# sparkfun_esp32_environment_sensor_shield.net
KiCad netlist of a schematic drawn in EAGLE
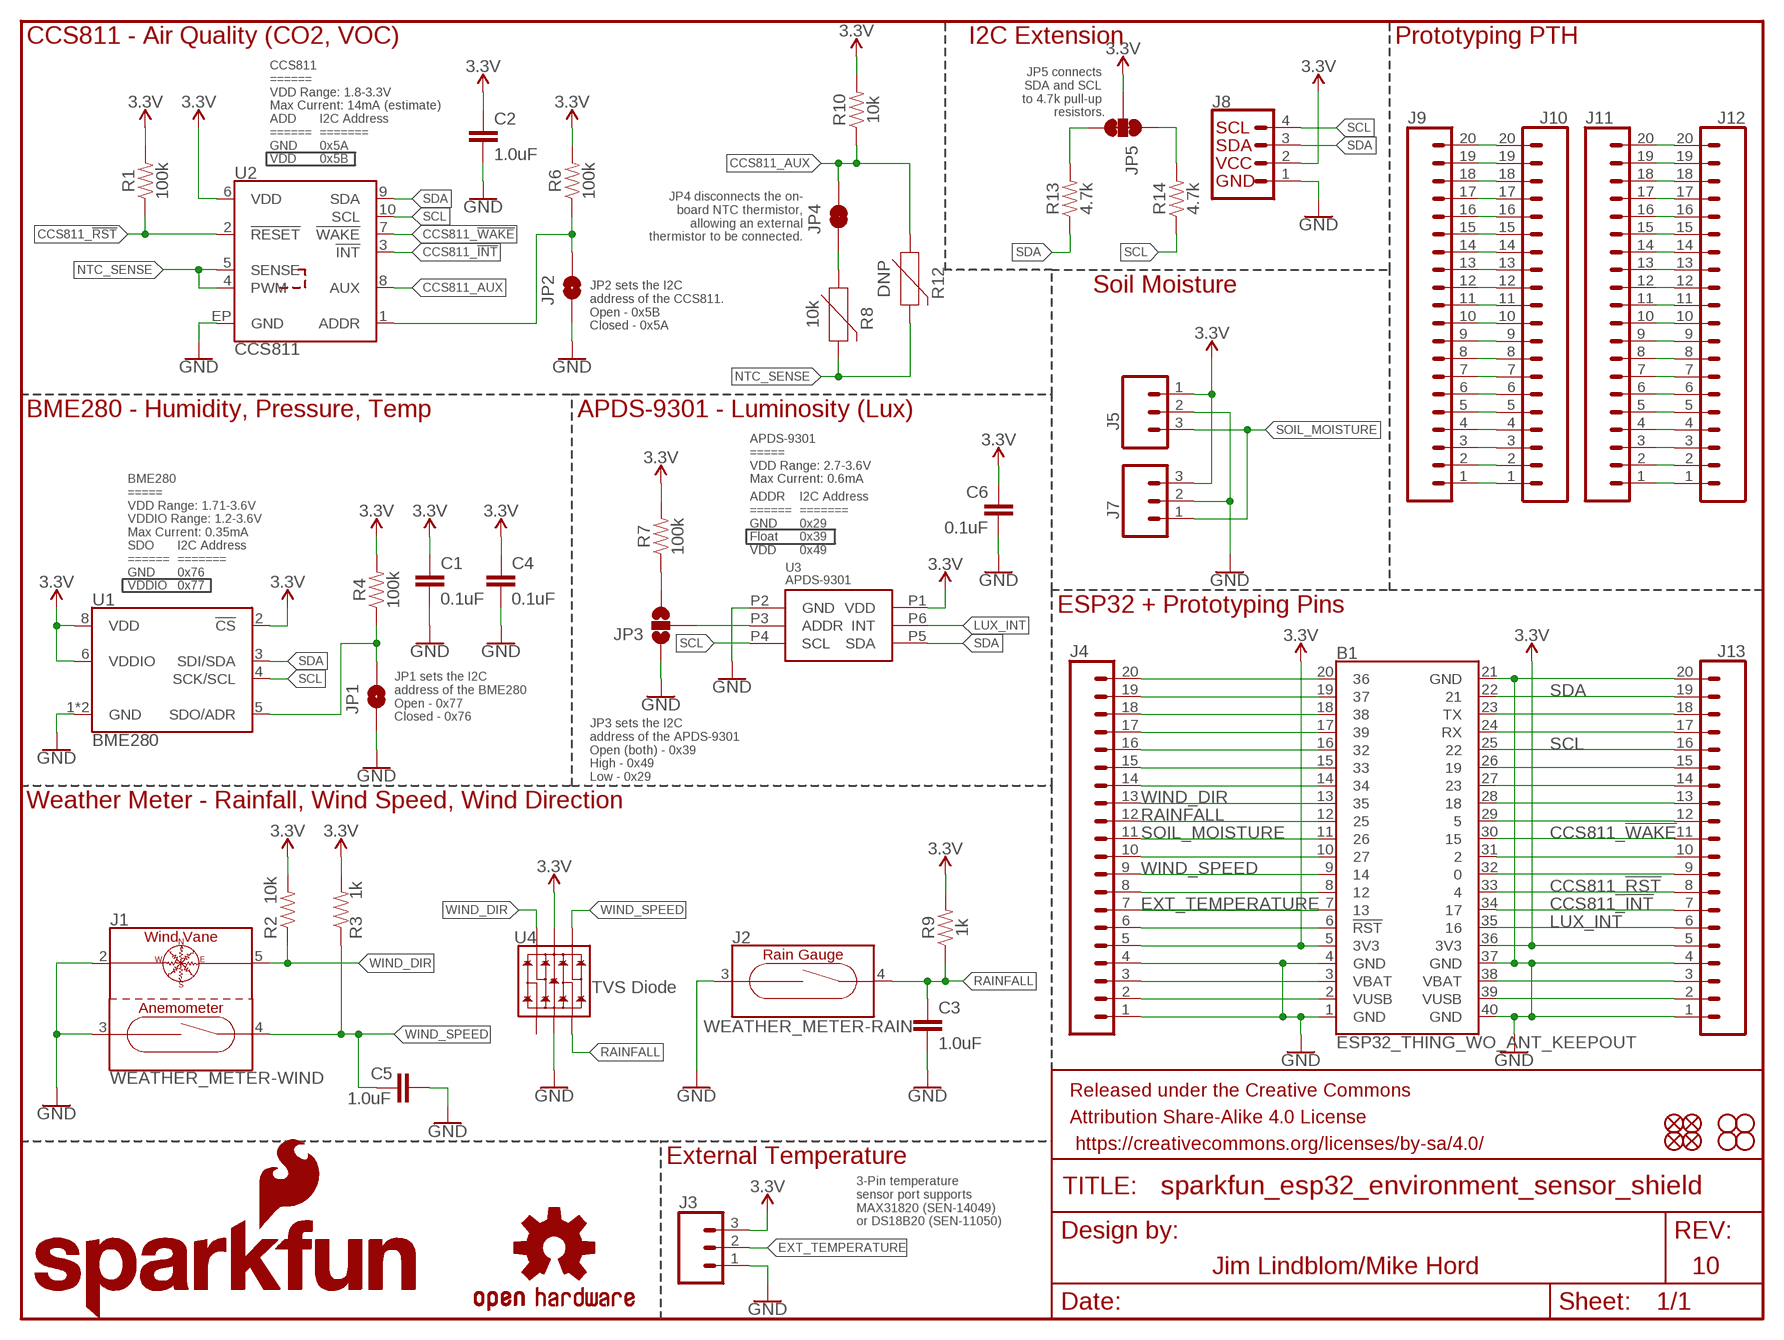
[diagram p0: schematic, sheet 1]

(export (version "E")
  (design (tool "Eeschema 10.0.6"))
  (components
    (comp (ref "B1")
      (value "ESP32_THING_WO_ANT_KEEPOUT")
      (footprint "eagle-import:ESP32_THING_NO_ANT")
      (libsource (lib "eagle-import") (part "ESP32_THING_WO_ANT_KEEPOUT"))
    )
    (comp (ref "C1")
      (value "0.1uF")
      (footprint "eagle-import:0603")
      (libsource (lib "eagle-import") (part "0.1UF-0603-25V-(+80/-20%)"))
    )
    (comp (ref "C2")
      (value "1.0uF")
      (footprint "eagle-import:0603")
      (libsource (lib "eagle-import") (part "1.0UF-0603-16V-10%"))
    )
    (comp (ref "C3")
      (value "1.0uF")
      (footprint "eagle-import:0603")
      (libsource (lib "eagle-import") (part "1.0UF-0603-16V-10%"))
    )
    (comp (ref "C4")
      (value "0.1uF")
      (footprint "eagle-import:0603")
      (libsource (lib "eagle-import") (part "0.1UF-0603-25V-(+80/-20%)"))
    )
    (comp (ref "C5")
      (value "1.0uF")
      (footprint "eagle-import:0603")
      (libsource (lib "eagle-import") (part "1.0UF-0603-16V-10%"))
    )
    (comp (ref "C6")
      (value "0.1uF")
      (footprint "eagle-import:0603")
      (libsource (lib "eagle-import") (part "0.1UF-0603-25V-(+80/-20%)"))
    )
    (comp (ref "FD1")
      (value "FIDUCIAL1X2")
      (footprint "eagle-import:FIDUCIAL-1X2")
      (libsource (lib "eagle-import") (part "FIDUCIAL1X2"))
    )
    (comp (ref "FD2")
      (value "FIDUCIAL1X2")
      (footprint "eagle-import:FIDUCIAL-1X2")
      (libsource (lib "eagle-import") (part "FIDUCIAL1X2"))
    )
    (comp (ref "FD3")
      (value "FIDUCIAL1X2")
      (footprint "eagle-import:FIDUCIAL-1X2")
      (libsource (lib "eagle-import") (part "FIDUCIAL1X2"))
    )
    (comp (ref "FD4")
      (value "FIDUCIAL1X2")
      (footprint "eagle-import:FIDUCIAL-1X2")
      (libsource (lib "eagle-import") (part "FIDUCIAL1X2"))
    )
    (comp (ref "FRAME1")
      (value "FRAME-LETTER")
      (footprint "eagle-import:CREATIVE_COMMONS")
      (libsource (lib "eagle-import") (part "FRAME-LETTER"))
    )
    (comp (ref "H1")
      (value "STAND-OFF")
      (footprint "eagle-import:STAND-OFF")
      (libsource (lib "eagle-import") (part "STAND-OFF"))
    )
    (comp (ref "H2")
      (value "STAND-OFF")
      (footprint "eagle-import:STAND-OFF")
      (libsource (lib "eagle-import") (part "STAND-OFF"))
    )
    (comp (ref "H3")
      (value "STAND-OFF")
      (footprint "eagle-import:STAND-OFF")
      (libsource (lib "eagle-import") (part "STAND-OFF"))
    )
    (comp (ref "H4")
      (value "STAND-OFF")
      (footprint "eagle-import:STAND-OFF")
      (libsource (lib "eagle-import") (part "STAND-OFF"))
    )
    (comp (ref "J1")
      (value "WEATHER_METER-WIND")
      (footprint "eagle-import:RJ11-6")
      (libsource (lib "eagle-import") (part "WEATHER_METER-WIND"))
    )
    (comp (ref "J2")
      (value "WEATHER_METER-RAIN")
      (footprint "eagle-import:RJ11-6")
      (libsource (lib "eagle-import") (part "WEATHER_METER-RAIN"))
    )
    (comp (ref "J3")
      (value "CONN_03")
      (footprint "eagle-import:1X03")
      (libsource (lib "eagle-import") (part "CONN_03"))
    )
    (comp (ref "J4")
      (value "CONN_20NOSILK")
      (footprint "eagle-import:1X20_NOSILK")
      (libsource (lib "eagle-import") (part "CONN_20NOSILK"))
    )
    (comp (ref "J5")
      (value "CONN_03")
      (footprint "eagle-import:1X03")
      (libsource (lib "eagle-import") (part "CONN_03"))
    )
    (comp (ref "J7")
      (value "CONN_03SCREW-NS")
      (footprint "eagle-import:SCREWTERMINAL-3.5MM-3-NS")
      (libsource (lib "eagle-import") (part "CONN_03SCREW-NS"))
    )
    (comp (ref "J8")
      (value "I2C_STANDARD")
      (footprint "eagle-import:1X04")
      (libsource (lib "eagle-import") (part "I2C_STANDARD"))
    )
    (comp (ref "J9")
      (value "CONN_20NOSILK")
      (footprint "eagle-import:1X20_NOSILK")
      (libsource (lib "eagle-import") (part "CONN_20NOSILK"))
    )
    (comp (ref "J10")
      (value "CONN_20NOSILK")
      (footprint "eagle-import:1X20_NOSILK")
      (libsource (lib "eagle-import") (part "CONN_20NOSILK"))
    )
    (comp (ref "J11")
      (value "CONN_20NOSILK")
      (footprint "eagle-import:1X20_NOSILK")
      (libsource (lib "eagle-import") (part "CONN_20NOSILK"))
    )
    (comp (ref "J12")
      (value "CONN_20NOSILK")
      (footprint "eagle-import:1X20_NOSILK")
      (libsource (lib "eagle-import") (part "CONN_20NOSILK"))
    )
    (comp (ref "J13")
      (value "CONN_20NOSILK")
      (footprint "eagle-import:1X20_NOSILK")
      (libsource (lib "eagle-import") (part "CONN_20NOSILK"))
    )
    (comp (ref "JP1")
      (value "JUMPER-SMT_2_NO_SILK")
      (footprint "eagle-import:SMT-JUMPER_2_NO_SILK")
      (libsource (lib "eagle-import") (part "JUMPER-SMT_2_NO_SILK"))
    )
    (comp (ref "JP2")
      (value "JUMPER-SMT_2_NO_SILK")
      (footprint "eagle-import:SMT-JUMPER_2_NO_SILK")
      (libsource (lib "eagle-import") (part "JUMPER-SMT_2_NO_SILK"))
    )
    (comp (ref "JP3")
      (value "JUMPER-SMT_3_NO_SILK")
      (footprint "eagle-import:SMT-JUMPER_3_NO_SILK")
      (libsource (lib "eagle-import") (part "JUMPER-SMT_3_NO_SILK"))
    )
    (comp (ref "JP4")
      (value "JUMPER-SMT_2_NC_TRACE_SILK")
      (footprint "eagle-import:SMT-JUMPER_2_NC_TRACE_SILK")
      (libsource (lib "eagle-import") (part "JUMPER-SMT_2_NC_TRACE_SILK"))
    )
    (comp (ref "JP5")
      (value "JUMPER-SMT_3_2-NC_TRACE_SILK")
      (footprint "eagle-import:SMT-JUMPER_3_2-NC_TRACE_SILK")
      (libsource (lib "eagle-import") (part "JUMPER-SMT_3_2-NC_TRACE_SILK"))
    )
    (comp (ref "LOGO1")
      (value "SFE_LOGO_NAME.1_INCH")
      (footprint "eagle-import:SFE_LOGO_NAME_.1")
      (libsource (lib "eagle-import") (part "SFE_LOGO_NAME.1_INCH"))
    )
    (comp (ref "LOGO2")
      (value "SFE_LOGO_NAME_FLAME.1_INCH")
      (footprint "eagle-import:SFE_LOGO_NAME_FLAME_.1")
      (libsource (lib "eagle-import") (part "SFE_LOGO_NAME_FLAME.1_INCH"))
    )
    (comp (ref "LOGO3")
      (value "SFE_LOGO_FLAME.1_INCH")
      (footprint "eagle-import:SFE_LOGO_FLAME_.1")
      (libsource (lib "eagle-import") (part "SFE_LOGO_FLAME.1_INCH"))
    )
    (comp (ref "LOGO4")
      (value "OSHW-LOGOS")
      (footprint "eagle-import:OSHW-LOGO-S")
      (libsource (lib "eagle-import") (part "OSHW-LOGOS"))
    )
    (comp (ref "R1")
      (value "100k")
      (footprint "eagle-import:0603")
      (libsource (lib "eagle-import") (part "100KOHM-0603-1/10W-1%"))
    )
    (comp (ref "R2")
      (value "10k")
      (footprint "eagle-import:0603")
      (libsource (lib "eagle-import") (part "10KOHM-0603-1/10W-1%"))
    )
    (comp (ref "R3")
      (value "1k")
      (footprint "eagle-import:0603")
      (libsource (lib "eagle-import") (part "1KOHM-0603-1/10W-1%"))
    )
    (comp (ref "R4")
      (value "100k")
      (footprint "eagle-import:0603")
      (libsource (lib "eagle-import") (part "100KOHM-0603-1/10W-1%"))
    )
    (comp (ref "R6")
      (value "100k")
      (footprint "eagle-import:0603")
      (libsource (lib "eagle-import") (part "100KOHM-0603-1/10W-1%"))
    )
    (comp (ref "R7")
      (value "100k")
      (footprint "eagle-import:0603")
      (libsource (lib "eagle-import") (part "100KOHM-0603-1/10W-1%"))
    )
    (comp (ref "R8")
      (value "10k")
      (footprint "eagle-import:0603")
      (libsource (lib "eagle-import") (part "NTC-THERMISTOR-0603"))
    )
    (comp (ref "R9")
      (value "1k")
      (footprint "eagle-import:0603")
      (libsource (lib "eagle-import") (part "1KOHM-0603-1/10W-1%"))
    )
    (comp (ref "R10")
      (value "10k")
      (footprint "eagle-import:0603")
      (libsource (lib "eagle-import") (part "10KOHM-0603-1/10W-1%"))
    )
    (comp (ref "R12")
      (value "DNP")
      (footprint "eagle-import:AXIAL-0.1")
      (libsource (lib "eagle-import") (part "NTC-THERMISTOR-AXIAL-0.1"))
    )
    (comp (ref "R13")
      (value "4.7k")
      (footprint "eagle-import:0603")
      (libsource (lib "eagle-import") (part "4.7KOHM-0603-1/10W-1%"))
    )
    (comp (ref "R14")
      (value "4.7k")
      (footprint "eagle-import:0603")
      (libsource (lib "eagle-import") (part "4.7KOHM-0603-1/10W-1%"))
    )
    (comp (ref "U1")
      (value "BME280")
      (footprint "eagle-import:LGA-8-2.5X2.5")
      (libsource (lib "eagle-import") (part "BME280"))
    )
    (comp (ref "U2")
      (value "CCS811")
      (footprint "eagle-import:LGA10-2.7X4.0MM")
      (libsource (lib "eagle-import") (part "CCS811"))
    )
    (comp (ref "U3")
      (value "APDS-9301")
      (footprint "eagle-import:CHIPLED-6")
      (libsource (lib "eagle-import") (part "APDS-9301"))
    )
    (comp (ref "U4")
      (value "TVS Diode")
      (footprint "eagle-import:SOT-23-6")
      (libsource (lib "eagle-import") (part "TVS_DIODE_ARRAYSMD"))
    )
  )
  (nets
    (net (code "1") (name "/CCS811_~{INT}") (class "Default")
      (node (ref "B1") (pin "34") (pinfunction "17_34") (pintype "bidirectional"))
      (node (ref "J13") (pin "7") (pinfunction "7_7") (pintype "passive"))
      (node (ref "U2") (pin "3") (pinfunction "~{INT}_3") (pintype "bidirectional"))
    )
    (net (code "2") (name "/CCS811_~{RST}") (class "Default")
      (node (ref "B1") (pin "33") (pinfunction "4_33") (pintype "bidirectional"))
      (node (ref "J13") (pin "8") (pinfunction "8_8") (pintype "passive"))
      (node (ref "R1") (pin "1") (pinfunction "1_1") (pintype "passive"))
      (node (ref "U2") (pin "2") (pinfunction "~{RESET}_2") (pintype "bidirectional"))
    )
    (net (code "3") (name "/CCS811_~{WAKE}") (class "Default")
      (node (ref "B1") (pin "30") (pinfunction "15_30") (pintype "bidirectional"))
      (node (ref "J13") (pin "11") (pinfunction "11_11") (pintype "passive"))
      (node (ref "U2") (pin "7") (pinfunction "~{WAKE}_7") (pintype "bidirectional"))
    )
    (net (code "4") (name "3.3V") (class "Default")
      (node (ref "B1") (pin "36") (pinfunction "3V3_36") (pintype "bidirectional"))
      (node (ref "B1") (pin "5") (pinfunction "3V3_5") (pintype "bidirectional"))
      (node (ref "C1") (pin "1") (pinfunction "1_1") (pintype "passive"))
      (node (ref "C2") (pin "1") (pinfunction "1_1") (pintype "passive"))
      (node (ref "C4") (pin "1") (pinfunction "1_1") (pintype "passive"))
      (node (ref "C6") (pin "1") (pinfunction "1_1") (pintype "passive"))
      (node (ref "J13") (pin "5") (pinfunction "5_5") (pintype "passive"))
      (node (ref "J3") (pin "3") (pinfunction "3_3") (pintype "passive"))
      (node (ref "J4") (pin "5") (pinfunction "5_5") (pintype "passive"))
      (node (ref "J5") (pin "1") (pinfunction "1_1") (pintype "passive"))
      (node (ref "J7") (pin "3") (pinfunction "3_3") (pintype "passive"))
      (node (ref "J8") (pin "2") (pinfunction "2_2") (pintype "power_in"))
      (node (ref "JP5") (pin "2") (pinfunction "2_2") (pintype "passive"))
      (node (ref "R1") (pin "2") (pinfunction "2_2") (pintype "passive"))
      (node (ref "R10") (pin "2") (pinfunction "2_2") (pintype "passive"))
      (node (ref "R2") (pin "2") (pinfunction "2_2") (pintype "passive"))
      (node (ref "R3") (pin "2") (pinfunction "2_2") (pintype "passive"))
      (node (ref "R4") (pin "2") (pinfunction "2_2") (pintype "passive"))
      (node (ref "R6") (pin "2") (pinfunction "2_2") (pintype "passive"))
      (node (ref "R7") (pin "2") (pinfunction "2_2") (pintype "passive"))
      (node (ref "R9") (pin "2") (pinfunction "2_2") (pintype "passive"))
      (node (ref "U1") (pin "2") (pinfunction "~{CS}_2") (pintype "bidirectional"))
      (node (ref "U1") (pin "6") (pinfunction "VDDIO_6") (pintype "bidirectional"))
      (node (ref "U1") (pin "8") (pinfunction "VDD_8") (pintype "bidirectional"))
      (node (ref "U2") (pin "6") (pinfunction "VDD_6") (pintype "bidirectional"))
      (node (ref "U3") (pin "P1") (pinfunction "VDD_P1") (pintype "bidirectional"))
      (node (ref "U4") (pin "5") (pinfunction "VCC_5") (pintype "bidirectional"))
    )
    (net (code "5") (name "CCS811_AUX") (class "Default")
      (node (ref "JP4") (pin "2") (pinfunction "2_2") (pintype "passive"))
      (node (ref "R10") (pin "1") (pinfunction "1_1") (pintype "passive"))
      (node (ref "R12") (pin "P$1") (pinfunction "1_P$1") (pintype "bidirectional"))
      (node (ref "U2") (pin "8") (pinfunction "AUX_8") (pintype "bidirectional"))
    )
    (net (code "6") (name "EXT_TEMPERATURE") (class "Default")
      (node (ref "B1") (pin "7") (pinfunction "13_7") (pintype "bidirectional"))
      (node (ref "J3") (pin "2") (pinfunction "2_2") (pintype "passive"))
      (node (ref "J4") (pin "7") (pinfunction "7_7") (pintype "passive"))
    )
    (net (code "7") (name "GND") (class "Default")
      (node (ref "B1") (pin "1") (pinfunction "GND_1") (pintype "bidirectional"))
      (node (ref "B1") (pin "21") (pinfunction "GND_21") (pintype "bidirectional"))
      (node (ref "B1") (pin "37") (pinfunction "GND_37") (pintype "bidirectional"))
      (node (ref "B1") (pin "4") (pinfunction "GND_4") (pintype "bidirectional"))
      (node (ref "B1") (pin "40") (pinfunction "GND_40") (pintype "bidirectional"))
      (node (ref "C1") (pin "2") (pinfunction "2_2") (pintype "passive"))
      (node (ref "C2") (pin "2") (pinfunction "2_2") (pintype "passive"))
      (node (ref "C3") (pin "2") (pinfunction "2_2") (pintype "passive"))
      (node (ref "C4") (pin "2") (pinfunction "2_2") (pintype "passive"))
      (node (ref "C5") (pin "2") (pinfunction "2_2") (pintype "passive"))
      (node (ref "C6") (pin "2") (pinfunction "2_2") (pintype "passive"))
      (node (ref "J1") (pin "2") (pinfunction "DIR-1_2") (pintype "bidirectional"))
      (node (ref "J1") (pin "3") (pinfunction "ANN-1_3") (pintype "bidirectional"))
      (node (ref "J13") (pin "1") (pinfunction "1_1") (pintype "passive"))
      (node (ref "J13") (pin "20") (pinfunction "20_20") (pintype "passive"))
      (node (ref "J13") (pin "4") (pinfunction "4_4") (pintype "passive"))
      (node (ref "J2") (pin "3") (pinfunction "1_3") (pintype "passive"))
      (node (ref "J3") (pin "1") (pinfunction "1_1") (pintype "passive"))
      (node (ref "J4") (pin "1") (pinfunction "1_1") (pintype "passive"))
      (node (ref "J4") (pin "4") (pinfunction "4_4") (pintype "passive"))
      (node (ref "J5") (pin "2") (pinfunction "2_2") (pintype "passive"))
      (node (ref "J7") (pin "2") (pinfunction "2_2") (pintype "passive"))
      (node (ref "J8") (pin "1") (pinfunction "1_1") (pintype "power_in"))
      (node (ref "JP1") (pin "1") (pinfunction "1_1") (pintype "passive"))
      (node (ref "JP2") (pin "1") (pinfunction "1_1") (pintype "passive"))
      (node (ref "JP3") (pin "1") (pinfunction "1_1") (pintype "passive"))
      (node (ref "U1") (pin "1") (pinfunction "GND_1") (pintype "bidirectional"))
      (node (ref "U1") (pin "7") (pinfunction "GND_7") (pintype "bidirectional"))
      (node (ref "U2") (pin "EP") (pinfunction "GND_EP") (pintype "bidirectional"))
      (node (ref "U3") (pin "P2") (pinfunction "GND_P2") (pintype "bidirectional"))
      (node (ref "U4") (pin "2") (pinfunction "VSS_2") (pintype "bidirectional"))
    )
    (net (code "8") (name "LUX_INT") (class "Default")
      (node (ref "B1") (pin "35") (pinfunction "16_35") (pintype "bidirectional"))
      (node (ref "J13") (pin "6") (pinfunction "6_6") (pintype "passive"))
      (node (ref "U3") (pin "P6") (pinfunction "INT_P6") (pintype "bidirectional"))
    )
    (net (code "9") (name "NTC_SENSE") (class "Default")
      (node (ref "R12") (pin "P$2") (pinfunction "2_P$2") (pintype "bidirectional"))
      (node (ref "R8") (pin "2") (pinfunction "2_2") (pintype "bidirectional"))
      (node (ref "U2") (pin "4") (pinfunction "PWM_4") (pintype "bidirectional"))
      (node (ref "U2") (pin "5") (pinfunction "SENSE_5") (pintype "bidirectional"))
    )
    (net (code "10") (name "Net-(B1-0)") (class "Default")
      (node (ref "B1") (pin "32") (pinfunction "0_32") (pintype "bidirectional"))
      (node (ref "J13") (pin "9") (pinfunction "9_9") (pintype "passive"))
    )
    (net (code "11") (name "Net-(B1-2)") (class "Default")
      (node (ref "B1") (pin "31") (pinfunction "2_31") (pintype "bidirectional"))
      (node (ref "J13") (pin "10") (pinfunction "10_10") (pintype "passive"))
    )
    (net (code "12") (name "Net-(B1-5)") (class "Default")
      (node (ref "B1") (pin "29") (pinfunction "5_29") (pintype "bidirectional"))
      (node (ref "J13") (pin "12") (pinfunction "12_12") (pintype "passive"))
    )
    (net (code "13") (name "Net-(B1-12)") (class "Default")
      (node (ref "B1") (pin "8") (pinfunction "12_8") (pintype "bidirectional"))
      (node (ref "J4") (pin "8") (pinfunction "8_8") (pintype "passive"))
    )
    (net (code "14") (name "Net-(B1-18)") (class "Default")
      (node (ref "B1") (pin "28") (pinfunction "18_28") (pintype "bidirectional"))
      (node (ref "J13") (pin "13") (pinfunction "13_13") (pintype "passive"))
    )
    (net (code "15") (name "Net-(B1-19)") (class "Default")
      (node (ref "B1") (pin "26") (pinfunction "19_26") (pintype "bidirectional"))
      (node (ref "J13") (pin "15") (pinfunction "15_15") (pintype "passive"))
    )
    (net (code "16") (name "Net-(B1-23)") (class "Default")
      (node (ref "B1") (pin "27") (pinfunction "23_27") (pintype "bidirectional"))
      (node (ref "J13") (pin "14") (pinfunction "14_14") (pintype "passive"))
    )
    (net (code "17") (name "Net-(B1-27)") (class "Default")
      (node (ref "B1") (pin "10") (pinfunction "27_10") (pintype "bidirectional"))
      (node (ref "J4") (pin "10") (pinfunction "10_10") (pintype "passive"))
    )
    (net (code "18") (name "Net-(B1-32)") (class "Default")
      (node (ref "B1") (pin "16") (pinfunction "32_16") (pintype "bidirectional"))
      (node (ref "J4") (pin "16") (pinfunction "16_16") (pintype "passive"))
    )
    (net (code "19") (name "Net-(B1-33)") (class "Default")
      (node (ref "B1") (pin "15") (pinfunction "33_15") (pintype "bidirectional"))
      (node (ref "J4") (pin "15") (pinfunction "15_15") (pintype "passive"))
    )
    (net (code "20") (name "Net-(B1-34)") (class "Default")
      (node (ref "B1") (pin "14") (pinfunction "34_14") (pintype "bidirectional"))
      (node (ref "J4") (pin "14") (pinfunction "14_14") (pintype "passive"))
    )
    (net (code "21") (name "Net-(B1-36)") (class "Default")
      (node (ref "B1") (pin "20") (pinfunction "36_20") (pintype "bidirectional"))
      (node (ref "J4") (pin "20") (pinfunction "20_20") (pintype "passive"))
    )
    (net (code "22") (name "Net-(B1-37)") (class "Default")
      (node (ref "B1") (pin "19") (pinfunction "37_19") (pintype "bidirectional"))
      (node (ref "J4") (pin "19") (pinfunction "19_19") (pintype "passive"))
    )
    (net (code "23") (name "Net-(B1-38)") (class "Default")
      (node (ref "B1") (pin "18") (pinfunction "38_18") (pintype "bidirectional"))
      (node (ref "J4") (pin "18") (pinfunction "18_18") (pintype "passive"))
    )
    (net (code "24") (name "Net-(B1-39)") (class "Default")
      (node (ref "B1") (pin "17") (pinfunction "39_17") (pintype "bidirectional"))
      (node (ref "J4") (pin "17") (pinfunction "17_17") (pintype "passive"))
    )
    (net (code "25") (name "Net-(B1-RX)") (class "Default")
      (node (ref "B1") (pin "24") (pinfunction "RX_24") (pintype "bidirectional"))
      (node (ref "J13") (pin "17") (pinfunction "17_17") (pintype "passive"))
    )
    (net (code "26") (name "Net-(B1-TX)") (class "Default")
      (node (ref "B1") (pin "23") (pinfunction "TX_23") (pintype "bidirectional"))
      (node (ref "J13") (pin "18") (pinfunction "18_18") (pintype "passive"))
    )
    (net (code "27") (name "Net-(B1-VBAT-Pad3)") (class "Default")
      (node (ref "B1") (pin "3") (pinfunction "VBAT_3") (pintype "bidirectional"))
      (node (ref "J4") (pin "3") (pinfunction "3_3") (pintype "passive"))
    )
    (net (code "28") (name "Net-(B1-VBAT-Pad38)") (class "Default")
      (node (ref "B1") (pin "38") (pinfunction "VBAT_38") (pintype "bidirectional"))
      (node (ref "J13") (pin "3") (pinfunction "3_3") (pintype "passive"))
    )
    (net (code "29") (name "Net-(B1-VUSB-Pad2)") (class "Default")
      (node (ref "B1") (pin "2") (pinfunction "VUSB_2") (pintype "bidirectional"))
      (node (ref "J4") (pin "2") (pinfunction "2_2") (pintype "passive"))
    )
    (net (code "30") (name "Net-(B1-VUSB-Pad39)") (class "Default")
      (node (ref "B1") (pin "39") (pinfunction "VUSB_39") (pintype "bidirectional"))
      (node (ref "J13") (pin "2") (pinfunction "2_2") (pintype "passive"))
    )
    (net (code "31") (name "Net-(B1-~{RST})") (class "Default")
      (node (ref "B1") (pin "6") (pinfunction "~{RST}_6") (pintype "bidirectional"))
      (node (ref "J4") (pin "6") (pinfunction "6_6") (pintype "passive"))
    )
    (net (code "32") (name "Net-(J10-Pad1)") (class "Default")
      (node (ref "J10") (pin "1") (pinfunction "1_1") (pintype "passive"))
      (node (ref "J9") (pin "1") (pinfunction "1_1") (pintype "passive"))
    )
    (net (code "33") (name "Net-(J10-Pad2)") (class "Default")
      (node (ref "J10") (pin "2") (pinfunction "2_2") (pintype "passive"))
      (node (ref "J9") (pin "2") (pinfunction "2_2") (pintype "passive"))
    )
    (net (code "34") (name "Net-(J10-Pad3)") (class "Default")
      (node (ref "J10") (pin "3") (pinfunction "3_3") (pintype "passive"))
      (node (ref "J9") (pin "3") (pinfunction "3_3") (pintype "passive"))
    )
    (net (code "35") (name "Net-(J10-Pad4)") (class "Default")
      (node (ref "J10") (pin "4") (pinfunction "4_4") (pintype "passive"))
      (node (ref "J9") (pin "4") (pinfunction "4_4") (pintype "passive"))
    )
    (net (code "36") (name "Net-(J10-Pad5)") (class "Default")
      (node (ref "J10") (pin "5") (pinfunction "5_5") (pintype "passive"))
      (node (ref "J9") (pin "5") (pinfunction "5_5") (pintype "passive"))
    )
    (net (code "37") (name "Net-(J10-Pad6)") (class "Default")
      (node (ref "J10") (pin "6") (pinfunction "6_6") (pintype "passive"))
      (node (ref "J9") (pin "6") (pinfunction "6_6") (pintype "passive"))
    )
    (net (code "38") (name "Net-(J10-Pad7)") (class "Default")
      (node (ref "J10") (pin "7") (pinfunction "7_7") (pintype "passive"))
      (node (ref "J9") (pin "7") (pinfunction "7_7") (pintype "passive"))
    )
    (net (code "39") (name "Net-(J10-Pad8)") (class "Default")
      (node (ref "J10") (pin "8") (pinfunction "8_8") (pintype "passive"))
      (node (ref "J9") (pin "8") (pinfunction "8_8") (pintype "passive"))
    )
    (net (code "40") (name "Net-(J10-Pad9)") (class "Default")
      (node (ref "J10") (pin "9") (pinfunction "9_9") (pintype "passive"))
      (node (ref "J9") (pin "9") (pinfunction "9_9") (pintype "passive"))
    )
    (net (code "41") (name "Net-(J10-Pad10)") (class "Default")
      (node (ref "J10") (pin "10") (pinfunction "10_10") (pintype "passive"))
      (node (ref "J9") (pin "10") (pinfunction "10_10") (pintype "passive"))
    )
    (net (code "42") (name "Net-(J10-Pad11)") (class "Default")
      (node (ref "J10") (pin "11") (pinfunction "11_11") (pintype "passive"))
      (node (ref "J9") (pin "11") (pinfunction "11_11") (pintype "passive"))
    )
    (net (code "43") (name "Net-(J10-Pad12)") (class "Default")
      (node (ref "J10") (pin "12") (pinfunction "12_12") (pintype "passive"))
      (node (ref "J9") (pin "12") (pinfunction "12_12") (pintype "passive"))
    )
    (net (code "44") (name "Net-(J10-Pad13)") (class "Default")
      (node (ref "J10") (pin "13") (pinfunction "13_13") (pintype "passive"))
      (node (ref "J9") (pin "13") (pinfunction "13_13") (pintype "passive"))
    )
    (net (code "45") (name "Net-(J10-Pad14)") (class "Default")
      (node (ref "J10") (pin "14") (pinfunction "14_14") (pintype "passive"))
      (node (ref "J9") (pin "14") (pinfunction "14_14") (pintype "passive"))
    )
    (net (code "46") (name "Net-(J10-Pad15)") (class "Default")
      (node (ref "J10") (pin "15") (pinfunction "15_15") (pintype "passive"))
      (node (ref "J9") (pin "15") (pinfunction "15_15") (pintype "passive"))
    )
    (net (code "47") (name "Net-(J10-Pad16)") (class "Default")
      (node (ref "J10") (pin "16") (pinfunction "16_16") (pintype "passive"))
      (node (ref "J9") (pin "16") (pinfunction "16_16") (pintype "passive"))
    )
    (net (code "48") (name "Net-(J10-Pad17)") (class "Default")
      (node (ref "J10") (pin "17") (pinfunction "17_17") (pintype "passive"))
      (node (ref "J9") (pin "17") (pinfunction "17_17") (pintype "passive"))
    )
    (net (code "49") (name "Net-(J10-Pad18)") (class "Default")
      (node (ref "J10") (pin "18") (pinfunction "18_18") (pintype "passive"))
      (node (ref "J9") (pin "18") (pinfunction "18_18") (pintype "passive"))
    )
    (net (code "50") (name "Net-(J10-Pad19)") (class "Default")
      (node (ref "J10") (pin "19") (pinfunction "19_19") (pintype "passive"))
      (node (ref "J9") (pin "19") (pinfunction "19_19") (pintype "passive"))
    )
    (net (code "51") (name "Net-(J10-Pad20)") (class "Default")
      (node (ref "J10") (pin "20") (pinfunction "20_20") (pintype "passive"))
      (node (ref "J9") (pin "20") (pinfunction "20_20") (pintype "passive"))
    )
    (net (code "52") (name "Net-(J11-Pad1)") (class "Default")
      (node (ref "J11") (pin "1") (pinfunction "1_1") (pintype "passive"))
      (node (ref "J12") (pin "1") (pinfunction "1_1") (pintype "passive"))
    )
    (net (code "53") (name "Net-(J11-Pad2)") (class "Default")
      (node (ref "J11") (pin "2") (pinfunction "2_2") (pintype "passive"))
      (node (ref "J12") (pin "2") (pinfunction "2_2") (pintype "passive"))
    )
    (net (code "54") (name "Net-(J11-Pad3)") (class "Default")
      (node (ref "J11") (pin "3") (pinfunction "3_3") (pintype "passive"))
      (node (ref "J12") (pin "3") (pinfunction "3_3") (pintype "passive"))
    )
    (net (code "55") (name "Net-(J11-Pad4)") (class "Default")
      (node (ref "J11") (pin "4") (pinfunction "4_4") (pintype "passive"))
      (node (ref "J12") (pin "4") (pinfunction "4_4") (pintype "passive"))
    )
    (net (code "56") (name "Net-(J11-Pad5)") (class "Default")
      (node (ref "J11") (pin "5") (pinfunction "5_5") (pintype "passive"))
      (node (ref "J12") (pin "5") (pinfunction "5_5") (pintype "passive"))
    )
    (net (code "57") (name "Net-(J11-Pad6)") (class "Default")
      (node (ref "J11") (pin "6") (pinfunction "6_6") (pintype "passive"))
      (node (ref "J12") (pin "6") (pinfunction "6_6") (pintype "passive"))
    )
    (net (code "58") (name "Net-(J11-Pad7)") (class "Default")
      (node (ref "J11") (pin "7") (pinfunction "7_7") (pintype "passive"))
      (node (ref "J12") (pin "7") (pinfunction "7_7") (pintype "passive"))
    )
    (net (code "59") (name "Net-(J11-Pad8)") (class "Default")
      (node (ref "J11") (pin "8") (pinfunction "8_8") (pintype "passive"))
      (node (ref "J12") (pin "8") (pinfunction "8_8") (pintype "passive"))
    )
    (net (code "60") (name "Net-(J11-Pad9)") (class "Default")
      (node (ref "J11") (pin "9") (pinfunction "9_9") (pintype "passive"))
      (node (ref "J12") (pin "9") (pinfunction "9_9") (pintype "passive"))
    )
    (net (code "61") (name "Net-(J11-Pad10)") (class "Default")
      (node (ref "J11") (pin "10") (pinfunction "10_10") (pintype "passive"))
      (node (ref "J12") (pin "10") (pinfunction "10_10") (pintype "passive"))
    )
    (net (code "62") (name "Net-(J11-Pad11)") (class "Default")
      (node (ref "J11") (pin "11") (pinfunction "11_11") (pintype "passive"))
      (node (ref "J12") (pin "11") (pinfunction "11_11") (pintype "passive"))
    )
    (net (code "63") (name "Net-(J11-Pad12)") (class "Default")
      (node (ref "J11") (pin "12") (pinfunction "12_12") (pintype "passive"))
      (node (ref "J12") (pin "12") (pinfunction "12_12") (pintype "passive"))
    )
    (net (code "64") (name "Net-(J11-Pad13)") (class "Default")
      (node (ref "J11") (pin "13") (pinfunction "13_13") (pintype "passive"))
      (node (ref "J12") (pin "13") (pinfunction "13_13") (pintype "passive"))
    )
    (net (code "65") (name "Net-(J11-Pad14)") (class "Default")
      (node (ref "J11") (pin "14") (pinfunction "14_14") (pintype "passive"))
      (node (ref "J12") (pin "14") (pinfunction "14_14") (pintype "passive"))
    )
    (net (code "66") (name "Net-(J11-Pad15)") (class "Default")
      (node (ref "J11") (pin "15") (pinfunction "15_15") (pintype "passive"))
      (node (ref "J12") (pin "15") (pinfunction "15_15") (pintype "passive"))
    )
    (net (code "67") (name "Net-(J11-Pad16)") (class "Default")
      (node (ref "J11") (pin "16") (pinfunction "16_16") (pintype "passive"))
      (node (ref "J12") (pin "16") (pinfunction "16_16") (pintype "passive"))
    )
    (net (code "68") (name "Net-(J11-Pad17)") (class "Default")
      (node (ref "J11") (pin "17") (pinfunction "17_17") (pintype "passive"))
      (node (ref "J12") (pin "17") (pinfunction "17_17") (pintype "passive"))
    )
    (net (code "69") (name "Net-(J11-Pad18)") (class "Default")
      (node (ref "J11") (pin "18") (pinfunction "18_18") (pintype "passive"))
      (node (ref "J12") (pin "18") (pinfunction "18_18") (pintype "passive"))
    )
    (net (code "70") (name "Net-(J11-Pad19)") (class "Default")
      (node (ref "J11") (pin "19") (pinfunction "19_19") (pintype "passive"))
      (node (ref "J12") (pin "19") (pinfunction "19_19") (pintype "passive"))
    )
    (net (code "71") (name "Net-(J11-Pad20)") (class "Default")
      (node (ref "J11") (pin "20") (pinfunction "20_20") (pintype "passive"))
      (node (ref "J12") (pin "20") (pinfunction "20_20") (pintype "passive"))
    )
    (net (code "72") (name "Net-(JP3-Pad3)") (class "Default")
      (node (ref "JP3") (pin "3") (pinfunction "3_3") (pintype "passive"))
      (node (ref "R7") (pin "1") (pinfunction "1_1") (pintype "passive"))
    )
    (net (code "73") (name "Net-(JP4-Pad1)") (class "Default")
      (node (ref "JP4") (pin "1") (pinfunction "1_1") (pintype "passive"))
      (node (ref "R8") (pin "1") (pinfunction "1_1") (pintype "bidirectional"))
    )
    (net (code "74") (name "Net-(JP5-Pad1)") (class "Default")
      (node (ref "JP5") (pin "1") (pinfunction "1_1") (pintype "passive"))
      (node (ref "R14") (pin "2") (pinfunction "2_2") (pintype "passive"))
    )
    (net (code "75") (name "Net-(JP5-Pad3)") (class "Default")
      (node (ref "JP5") (pin "3") (pinfunction "3_3") (pintype "passive"))
      (node (ref "R13") (pin "2") (pinfunction "2_2") (pintype "passive"))
    )
    (net (code "76") (name "Net-(U1-SDO{slash}ADR)") (class "Default")
      (node (ref "JP1") (pin "2") (pinfunction "2_2") (pintype "passive"))
      (node (ref "R4") (pin "1") (pinfunction "1_1") (pintype "passive"))
      (node (ref "U1") (pin "5") (pinfunction "SDO/ADR_5") (pintype "bidirectional"))
    )
    (net (code "77") (name "Net-(U2-ADDR)") (class "Default")
      (node (ref "JP2") (pin "2") (pinfunction "2_2") (pintype "passive"))
      (node (ref "R6") (pin "1") (pinfunction "1_1") (pintype "passive"))
      (node (ref "U2") (pin "1") (pinfunction "ADDR_1") (pintype "bidirectional"))
    )
    (net (code "78") (name "Net-(U3-ADDR)") (class "Default")
      (node (ref "JP3") (pin "2") (pinfunction "2_2") (pintype "passive"))
      (node (ref "U3") (pin "P3") (pinfunction "ADDR_P3") (pintype "bidirectional"))
    )
    (net (code "79") (name "RAINFALL") (class "Default")
      (node (ref "B1") (pin "12") (pinfunction "25_12") (pintype "bidirectional"))
      (node (ref "C3") (pin "1") (pinfunction "1_1") (pintype "passive"))
      (node (ref "J2") (pin "4") (pinfunction "2_4") (pintype "passive"))
      (node (ref "J4") (pin "12") (pinfunction "12_12") (pintype "passive"))
      (node (ref "R9") (pin "1") (pinfunction "1_1") (pintype "passive"))
      (node (ref "U4") (pin "3") (pinfunction "IO2_3") (pintype "bidirectional"))
    )
    (net (code "80") (name "SCL") (class "Default")
      (node (ref "B1") (pin "25") (pinfunction "22_25") (pintype "bidirectional"))
      (node (ref "J13") (pin "16") (pinfunction "16_16") (pintype "passive"))
      (node (ref "J8") (pin "4") (pinfunction "4_4") (pintype "passive"))
      (node (ref "R14") (pin "1") (pinfunction "1_1") (pintype "passive"))
      (node (ref "U1") (pin "4") (pinfunction "SCK/SCL_4") (pintype "bidirectional"))
      (node (ref "U2") (pin "10") (pinfunction "SCL_10") (pintype "bidirectional"))
      (node (ref "U3") (pin "P4") (pinfunction "SCL_P4") (pintype "bidirectional"))
    )
    (net (code "81") (name "SDA") (class "Default")
      (node (ref "B1") (pin "22") (pinfunction "21_22") (pintype "bidirectional"))
      (node (ref "J13") (pin "19") (pinfunction "19_19") (pintype "passive"))
      (node (ref "J8") (pin "3") (pinfunction "3_3") (pintype "passive"))
      (node (ref "R13") (pin "1") (pinfunction "1_1") (pintype "passive"))
      (node (ref "U1") (pin "3") (pinfunction "SDI/SDA_3") (pintype "bidirectional"))
      (node (ref "U2") (pin "9") (pinfunction "SDA_9") (pintype "bidirectional"))
      (node (ref "U3") (pin "P5") (pinfunction "SDA_P5") (pintype "bidirectional"))
    )
    (net (code "82") (name "SOIL_MOISTURE") (class "Default")
      (node (ref "B1") (pin "11") (pinfunction "26_11") (pintype "bidirectional"))
      (node (ref "J4") (pin "11") (pinfunction "11_11") (pintype "passive"))
      (node (ref "J5") (pin "3") (pinfunction "3_3") (pintype "passive"))
      (node (ref "J7") (pin "1") (pinfunction "1_1") (pintype "passive"))
    )
    (net (code "83") (name "WIND_DIR") (class "Default")
      (node (ref "B1") (pin "13") (pinfunction "35_13") (pintype "bidirectional"))
      (node (ref "J1") (pin "5") (pinfunction "DIR2_5") (pintype "bidirectional"))
      (node (ref "J4") (pin "13") (pinfunction "13_13") (pintype "passive"))
      (node (ref "R2") (pin "1") (pinfunction "1_1") (pintype "passive"))
      (node (ref "U4") (pin "6") (pinfunction "IO4_6") (pintype "bidirectional"))
    )
    (net (code "84") (name "WIND_SPEED") (class "Default")
      (node (ref "B1") (pin "9") (pinfunction "14_9") (pintype "bidirectional"))
      (node (ref "C5") (pin "1") (pinfunction "1_1") (pintype "passive"))
      (node (ref "J1") (pin "4") (pinfunction "ANN-2_4") (pintype "bidirectional"))
      (node (ref "J4") (pin "9") (pinfunction "9_9") (pintype "passive"))
      (node (ref "R3") (pin "1") (pinfunction "1_1") (pintype "passive"))
      (node (ref "U4") (pin "4") (pinfunction "IO3_4") (pintype "bidirectional"))
    )
    (net (code "85") (name "unconnected-(U4-IO1-Pad1)") (class "Default")
      (node (ref "U4") (pin "1") (pinfunction "IO1_1") (pintype "bidirectional"))
    )
  )
)
